# MI0283QT_v14.net
KiCad netlist of a schematic drawn in EAGLE
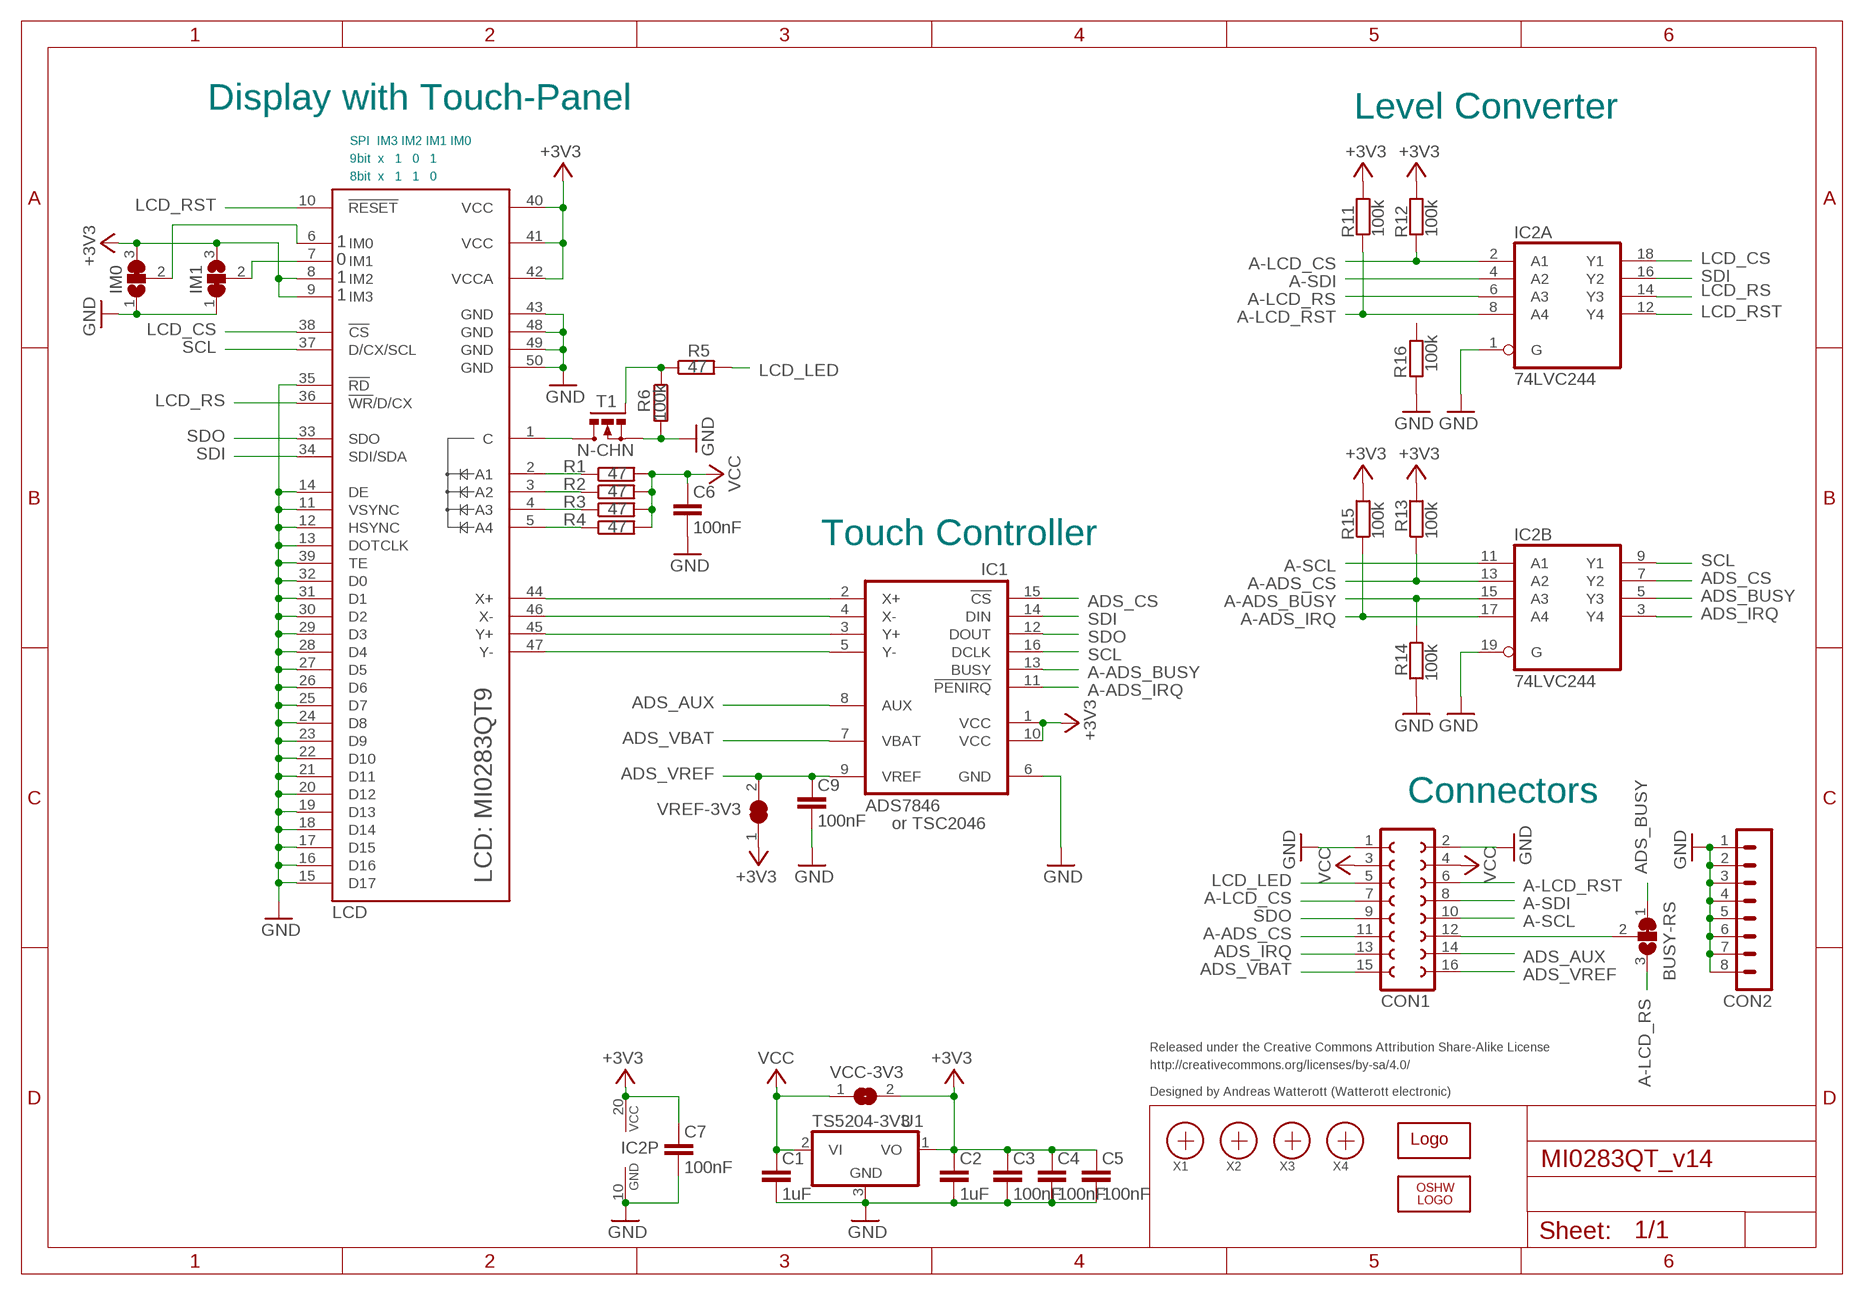
[diagram p0: schematic, sheet 1]

(export (version "E")
  (design (tool "Eeschema 10.0.6"))
  (components
    (comp (ref "BUSY-RS")
      (value "SJ2W")
      (footprint "eagle-import:SJ_2")
      (libsource (lib "eagle-import") (part "SJ2W"))
    )
    (comp (ref "C1")
      (value "1uF")
      (footprint "eagle-import:C0603")
      (libsource (lib "eagle-import") (part "C-EUC0603"))
    )
    (comp (ref "C2")
      (value "1uF")
      (footprint "eagle-import:C0603")
      (libsource (lib "eagle-import") (part "C-EUC0603"))
    )
    (comp (ref "C3")
      (value "100nF")
      (footprint "eagle-import:C0603")
      (libsource (lib "eagle-import") (part "C-EUC0603"))
    )
    (comp (ref "C4")
      (value "100nF")
      (footprint "eagle-import:C0603")
      (libsource (lib "eagle-import") (part "C-EUC0603"))
    )
    (comp (ref "C5")
      (value "100nF")
      (footprint "eagle-import:C0603")
      (libsource (lib "eagle-import") (part "C-EUC0603"))
    )
    (comp (ref "C6")
      (value "100nF")
      (footprint "eagle-import:C0603")
      (libsource (lib "eagle-import") (part "C-EUC0603"))
    )
    (comp (ref "C7")
      (value "100nF")
      (footprint "eagle-import:C0603")
      (libsource (lib "eagle-import") (part "C-EUC0603"))
    )
    (comp (ref "C9")
      (value "100nF")
      (footprint "eagle-import:C0603")
      (libsource (lib "eagle-import") (part "C-EUC0603"))
    )
    (comp (ref "CON1")
      (value "FE08-2")
      (footprint "eagle-import:FE08-2")
      (libsource (lib "eagle-import") (part "FE08-2"))
    )
    (comp (ref "CON2")
      (value "MA08-1")
      (footprint "eagle-import:MA08-1")
      (libsource (lib "eagle-import") (part "MA08-1"))
    )
    (comp (ref "IC1")
      (value "ADS7846")
      (footprint "eagle-import:SSOP16")
      (libsource (lib "eagle-import") (part "ADS7846"))
    )
    (comp (ref "IC2")
      (value "74LVC244")
      (footprint "eagle-import:SO20W")
      (libsource (lib "eagle-import") (part "74244DWHC"))
    )
    (comp (ref "IM0")
      (value "SJ2W")
      (footprint "eagle-import:SJ_2")
      (libsource (lib "eagle-import") (part "SJ2W"))
    )
    (comp (ref "IM1")
      (value "SJ2W")
      (footprint "eagle-import:SJ_2")
      (libsource (lib "eagle-import") (part "SJ2W"))
    )
    (comp (ref "LCD")
      (value "MI0283QT9")
      (footprint "eagle-import:MI0283QT9")
      (libsource (lib "eagle-import") (part "MI0283QT9"))
    )
    (comp (ref "LOGO1")
      (value "OSHW_LOGO_6MILX0150-NT")
      (footprint "eagle-import:OSHW_6X150_NOTEXT")
      (libsource (lib "eagle-import") (part "OSHW_LOGO_6MILX0150-NT"))
    )
    (comp (ref "R1")
      (value "47")
      (footprint "eagle-import:R0603")
      (libsource (lib "eagle-import") (part "R-EU_R0603"))
    )
    (comp (ref "R2")
      (value "47")
      (footprint "eagle-import:R0603")
      (libsource (lib "eagle-import") (part "R-EU_R0603"))
    )
    (comp (ref "R3")
      (value "47")
      (footprint "eagle-import:R0603")
      (libsource (lib "eagle-import") (part "R-EU_R0603"))
    )
    (comp (ref "R4")
      (value "47")
      (footprint "eagle-import:R0603")
      (libsource (lib "eagle-import") (part "R-EU_R0603"))
    )
    (comp (ref "R5")
      (value "47")
      (footprint "eagle-import:R0603")
      (libsource (lib "eagle-import") (part "R-EU_R0603"))
    )
    (comp (ref "R6")
      (value "100k")
      (footprint "eagle-import:R0603")
      (libsource (lib "eagle-import") (part "R-EU_R0603"))
    )
    (comp (ref "R11")
      (value "100k")
      (footprint "eagle-import:R0603")
      (libsource (lib "eagle-import") (part "R-EU_R0603"))
    )
    (comp (ref "R12")
      (value "100k")
      (footprint "eagle-import:R0603")
      (libsource (lib "eagle-import") (part "R-EU_R0603"))
    )
    (comp (ref "R13")
      (value "100k")
      (footprint "eagle-import:R0603")
      (libsource (lib "eagle-import") (part "R-EU_R0603"))
    )
    (comp (ref "R14")
      (value "100k")
      (footprint "eagle-import:R0603")
      (libsource (lib "eagle-import") (part "R-EU_R0603"))
    )
    (comp (ref "R15")
      (value "100k")
      (footprint "eagle-import:R0603")
      (libsource (lib "eagle-import") (part "R-EU_R0603"))
    )
    (comp (ref "R16")
      (value "100k")
      (footprint "eagle-import:R0603")
      (libsource (lib "eagle-import") (part "R-EU_R0603"))
    )
    (comp (ref "T1")
      (value "N-CHN")
      (footprint "eagle-import:MICRO3")
      (libsource (lib "eagle-import") (part "IRLML2502"))
    )
    (comp (ref "U$1")
      (value "WE-LOGO")
      (footprint "eagle-import:WE-LOGO")
      (libsource (lib "eagle-import") (part "WE-LOGOPLACE"))
    )
    (comp (ref "U1")
      (value "TS5204-3V3")
      (footprint "eagle-import:SOT23")
      (libsource (lib "eagle-import") (part "TS5204"))
    )
    (comp (ref "VCC-3V3")
      (value "SJ")
      (footprint "eagle-import:SJ")
      (libsource (lib "eagle-import") (part "SJ"))
    )
    (comp (ref "VREF-3V3")
      (value "SJ")
      (footprint "eagle-import:SJ")
      (libsource (lib "eagle-import") (part "SJ"))
    )
    (comp (ref "X1")
      (value "PASSER")
      (footprint "eagle-import:PASSER")
      (libsource (lib "eagle-import") (part "PASSER"))
    )
    (comp (ref "X2")
      (value "PASSER")
      (footprint "eagle-import:PASSER")
      (libsource (lib "eagle-import") (part "PASSER"))
    )
    (comp (ref "X3")
      (value "PASSER")
      (footprint "eagle-import:PASSER")
      (libsource (lib "eagle-import") (part "PASSER"))
    )
    (comp (ref "X4")
      (value "PASSER")
      (footprint "eagle-import:PASSER")
      (libsource (lib "eagle-import") (part "PASSER"))
    )
  )
  (nets
    (net (code "1") (name "+3V3") (class "Default")
      (node (ref "C2") (pin "1") (pinfunction "1_1") (pintype "passive"))
      (node (ref "C3") (pin "1") (pinfunction "1_1") (pintype "passive"))
      (node (ref "C4") (pin "1") (pinfunction "1_1") (pintype "passive"))
      (node (ref "C5") (pin "1") (pinfunction "1_1") (pintype "passive"))
      (node (ref "C7") (pin "1") (pinfunction "1_1") (pintype "passive"))
      (node (ref "IC1") (pin "1") (pinfunction "VCC_1") (pintype "power_in"))
      (node (ref "IC1") (pin "10") (pinfunction "VCC_10") (pintype "power_in"))
      (node (ref "IC2") (pin "20") (pinfunction "VCC_20") (pintype "power_in"))
      (node (ref "IM0") (pin "3") (pinfunction "3_3") (pintype "passive"))
      (node (ref "IM1") (pin "3") (pinfunction "3_3") (pintype "passive"))
      (node (ref "LCD") (pin "40") (pinfunction "VCC_40") (pintype "power_in"))
      (node (ref "LCD") (pin "41") (pinfunction "VCC_41") (pintype "power_in"))
      (node (ref "LCD") (pin "42") (pinfunction "VCCA_42") (pintype "power_in"))
      (node (ref "LCD") (pin "8") (pinfunction "IM2_8") (pintype "input"))
      (node (ref "LCD") (pin "9") (pinfunction "IM3_9") (pintype "input"))
      (node (ref "R11") (pin "2") (pinfunction "2_2") (pintype "passive"))
      (node (ref "R12") (pin "2") (pinfunction "2_2") (pintype "passive"))
      (node (ref "R13") (pin "2") (pinfunction "2_2") (pintype "passive"))
      (node (ref "R15") (pin "2") (pinfunction "2_2") (pintype "passive"))
      (node (ref "U1") (pin "1") (pinfunction "VO_1") (pintype "passive"))
      (node (ref "VCC-3V3") (pin "2") (pinfunction "2_2") (pintype "passive"))
      (node (ref "VREF-3V3") (pin "1") (pinfunction "1_1") (pintype "passive"))
    )
    (net (code "2") (name "/A-ADS_BUSY") (class "Default")
      (node (ref "IC1") (pin "13") (pinfunction "BUSY_13") (pintype "output"))
      (node (ref "IC2") (pin "15") (pinfunction "A3_15") (pintype "input"))
      (node (ref "R14") (pin "1") (pinfunction "1_1") (pintype "passive"))
    )
    (net (code "3") (name "/A-ADS_CS") (class "Default")
      (node (ref "CON1") (pin "11") (pinfunction "11_11") (pintype "passive"))
      (node (ref "IC2") (pin "13") (pinfunction "A2_13") (pintype "input"))
      (node (ref "R13") (pin "1") (pinfunction "1_1") (pintype "passive"))
    )
    (net (code "4") (name "/A-ADS_IRQ") (class "Default")
      (node (ref "IC1") (pin "11") (pinfunction "~{PENIRQ}_11") (pintype "output"))
      (node (ref "IC2") (pin "17") (pinfunction "A4_17") (pintype "input"))
      (node (ref "R15") (pin "1") (pinfunction "1_1") (pintype "passive"))
    )
    (net (code "5") (name "/A-LCD_CS") (class "Default")
      (node (ref "CON1") (pin "7") (pinfunction "7_7") (pintype "passive"))
      (node (ref "IC2") (pin "2") (pinfunction "A1_2") (pintype "input"))
      (node (ref "R12") (pin "1") (pinfunction "1_1") (pintype "passive"))
    )
    (net (code "6") (name "/A-LCD_RS") (class "Default")
      (node (ref "BUSY-RS") (pin "3") (pinfunction "3_3") (pintype "passive"))
      (node (ref "IC2") (pin "6") (pinfunction "A3_6") (pintype "input"))
    )
    (net (code "7") (name "/A-LCD_RST") (class "Default")
      (node (ref "CON1") (pin "6") (pinfunction "6_6") (pintype "passive"))
      (node (ref "IC2") (pin "8") (pinfunction "A4_8") (pintype "input"))
      (node (ref "R11") (pin "1") (pinfunction "1_1") (pintype "passive"))
    )
    (net (code "8") (name "/A-SCL") (class "Default")
      (node (ref "CON1") (pin "10") (pinfunction "10_10") (pintype "passive"))
      (node (ref "IC2") (pin "11") (pinfunction "A1_11") (pintype "input"))
    )
    (net (code "9") (name "/A-SDI") (class "Default")
      (node (ref "CON1") (pin "8") (pinfunction "8_8") (pintype "passive"))
      (node (ref "IC2") (pin "4") (pinfunction "A2_4") (pintype "input"))
    )
    (net (code "10") (name "/ADS_AUX") (class "Default")
      (node (ref "CON1") (pin "14") (pinfunction "14_14") (pintype "passive"))
      (node (ref "IC1") (pin "8") (pinfunction "AUX_8") (pintype "input"))
    )
    (net (code "11") (name "/ADS_BUSY") (class "Default")
      (node (ref "BUSY-RS") (pin "1") (pinfunction "1_1") (pintype "passive"))
      (node (ref "IC2") (pin "5") (pinfunction "Y3_5") (pintype "tri_state"))
    )
    (net (code "12") (name "/ADS_CS") (class "Default")
      (node (ref "IC1") (pin "15") (pinfunction "~{CS}_15") (pintype "input"))
      (node (ref "IC2") (pin "7") (pinfunction "Y2_7") (pintype "tri_state"))
    )
    (net (code "13") (name "/ADS_IRQ") (class "Default")
      (node (ref "CON1") (pin "13") (pinfunction "13_13") (pintype "passive"))
      (node (ref "IC2") (pin "3") (pinfunction "Y4_3") (pintype "tri_state"))
    )
    (net (code "14") (name "/ADS_VBAT") (class "Default")
      (node (ref "CON1") (pin "15") (pinfunction "15_15") (pintype "passive"))
      (node (ref "IC1") (pin "7") (pinfunction "VBAT_7") (pintype "input"))
    )
    (net (code "15") (name "/ADS_VREF") (class "Default")
      (node (ref "C9") (pin "1") (pinfunction "1_1") (pintype "passive"))
      (node (ref "CON1") (pin "16") (pinfunction "16_16") (pintype "passive"))
      (node (ref "IC1") (pin "9") (pinfunction "VREF_9") (pintype "bidirectional"))
      (node (ref "VREF-3V3") (pin "2") (pinfunction "2_2") (pintype "passive"))
    )
    (net (code "16") (name "/LCD_CS") (class "Default")
      (node (ref "IC2") (pin "18") (pinfunction "Y1_18") (pintype "tri_state"))
      (node (ref "LCD") (pin "38") (pinfunction "~{CS}_38") (pintype "input"))
    )
    (net (code "17") (name "/LCD_LED") (class "Default")
      (node (ref "CON1") (pin "5") (pinfunction "5_5") (pintype "passive"))
      (node (ref "R5") (pin "2") (pinfunction "2_2") (pintype "passive"))
    )
    (net (code "18") (name "/LCD_RS") (class "Default")
      (node (ref "IC2") (pin "14") (pinfunction "Y3_14") (pintype "tri_state"))
      (node (ref "LCD") (pin "36") (pinfunction "~{WR}/D/CX_36") (pintype "input"))
    )
    (net (code "19") (name "/LCD_RST") (class "Default")
      (node (ref "IC2") (pin "12") (pinfunction "Y4_12") (pintype "tri_state"))
      (node (ref "LCD") (pin "10") (pinfunction "~{RESET}_10") (pintype "input"))
    )
    (net (code "20") (name "/SCL") (class "Default")
      (node (ref "IC1") (pin "16") (pinfunction "DCLK_16") (pintype "output"))
      (node (ref "IC2") (pin "9") (pinfunction "Y1_9") (pintype "tri_state"))
      (node (ref "LCD") (pin "37") (pinfunction "D/CX/SCL_37") (pintype "input"))
    )
    (net (code "21") (name "/SDI") (class "Default")
      (node (ref "IC1") (pin "14") (pinfunction "DIN_14") (pintype "input"))
      (node (ref "IC2") (pin "16") (pinfunction "Y2_16") (pintype "tri_state"))
      (node (ref "LCD") (pin "34") (pinfunction "SDI/SDA_34") (pintype "input"))
    )
    (net (code "22") (name "/SDO") (class "Default")
      (node (ref "CON1") (pin "9") (pinfunction "9_9") (pintype "passive"))
      (node (ref "IC1") (pin "12") (pinfunction "DOUT_12") (pintype "input"))
      (node (ref "LCD") (pin "33") (pinfunction "SDO_33") (pintype "output"))
    )
    (net (code "23") (name "GND") (class "Default")
      (node (ref "C1") (pin "2") (pinfunction "2_2") (pintype "passive"))
      (node (ref "C2") (pin "2") (pinfunction "2_2") (pintype "passive"))
      (node (ref "C3") (pin "2") (pinfunction "2_2") (pintype "passive"))
      (node (ref "C4") (pin "2") (pinfunction "2_2") (pintype "passive"))
      (node (ref "C5") (pin "2") (pinfunction "2_2") (pintype "passive"))
      (node (ref "C6") (pin "2") (pinfunction "2_2") (pintype "passive"))
      (node (ref "C7") (pin "2") (pinfunction "2_2") (pintype "passive"))
      (node (ref "C9") (pin "2") (pinfunction "2_2") (pintype "passive"))
      (node (ref "CON1") (pin "1") (pinfunction "1_1") (pintype "passive"))
      (node (ref "CON1") (pin "2") (pinfunction "2_2") (pintype "passive"))
      (node (ref "CON2") (pin "1") (pinfunction "1_1") (pintype "passive"))
      (node (ref "CON2") (pin "2") (pinfunction "2_2") (pintype "passive"))
      (node (ref "CON2") (pin "3") (pinfunction "3_3") (pintype "passive"))
      (node (ref "CON2") (pin "4") (pinfunction "4_4") (pintype "passive"))
      (node (ref "CON2") (pin "5") (pinfunction "5_5") (pintype "passive"))
      (node (ref "CON2") (pin "6") (pinfunction "6_6") (pintype "passive"))
      (node (ref "CON2") (pin "7") (pinfunction "7_7") (pintype "passive"))
      (node (ref "CON2") (pin "8") (pinfunction "8_8") (pintype "passive"))
      (node (ref "IC1") (pin "6") (pinfunction "GND_6") (pintype "power_in"))
      (node (ref "IC2") (pin "1") (pinfunction "G_1") (pintype "input"))
      (node (ref "IC2") (pin "10") (pinfunction "GND_10") (pintype "power_in"))
      (node (ref "IC2") (pin "19") (pinfunction "G_19") (pintype "input"))
      (node (ref "IM0") (pin "1") (pinfunction "1_1") (pintype "passive"))
      (node (ref "IM1") (pin "1") (pinfunction "1_1") (pintype "passive"))
      (node (ref "LCD") (pin "11") (pinfunction "VSYNC_11") (pintype "input"))
      (node (ref "LCD") (pin "12") (pinfunction "HSYNC_12") (pintype "input"))
      (node (ref "LCD") (pin "13") (pinfunction "DOTCLK_13") (pintype "input"))
      (node (ref "LCD") (pin "14") (pinfunction "DE_14") (pintype "input"))
      (node (ref "LCD") (pin "15") (pinfunction "D17_15") (pintype "input"))
      (node (ref "LCD") (pin "16") (pinfunction "D16_16") (pintype "input"))
      (node (ref "LCD") (pin "17") (pinfunction "D15_17") (pintype "input"))
      (node (ref "LCD") (pin "18") (pinfunction "D14_18") (pintype "input"))
      (node (ref "LCD") (pin "19") (pinfunction "D13_19") (pintype "input"))
      (node (ref "LCD") (pin "20") (pinfunction "D12_20") (pintype "input"))
      (node (ref "LCD") (pin "21") (pinfunction "D11_21") (pintype "input"))
      (node (ref "LCD") (pin "22") (pinfunction "D10_22") (pintype "input"))
      (node (ref "LCD") (pin "23") (pinfunction "D9_23") (pintype "input"))
      (node (ref "LCD") (pin "24") (pinfunction "D8_24") (pintype "input"))
      (node (ref "LCD") (pin "25") (pinfunction "D7_25") (pintype "input"))
      (node (ref "LCD") (pin "26") (pinfunction "D6_26") (pintype "input"))
      (node (ref "LCD") (pin "27") (pinfunction "D5_27") (pintype "input"))
      (node (ref "LCD") (pin "28") (pinfunction "D4_28") (pintype "input"))
      (node (ref "LCD") (pin "29") (pinfunction "D3_29") (pintype "input"))
      (node (ref "LCD") (pin "30") (pinfunction "D2_30") (pintype "input"))
      (node (ref "LCD") (pin "31") (pinfunction "D1_31") (pintype "input"))
      (node (ref "LCD") (pin "32") (pinfunction "D0_32") (pintype "input"))
      (node (ref "LCD") (pin "35") (pinfunction "~{RD}_35") (pintype "input"))
      (node (ref "LCD") (pin "39") (pinfunction "TE_39") (pintype "output"))
      (node (ref "LCD") (pin "43") (pinfunction "GND_43") (pintype "power_in"))
      (node (ref "LCD") (pin "48") (pinfunction "GND_48") (pintype "power_in"))
      (node (ref "LCD") (pin "49") (pinfunction "GND_49") (pintype "power_in"))
      (node (ref "LCD") (pin "50") (pinfunction "GND_50") (pintype "power_in"))
      (node (ref "R14") (pin "2") (pinfunction "2_2") (pintype "passive"))
      (node (ref "R16") (pin "2") (pinfunction "2_2") (pintype "passive"))
      (node (ref "R6") (pin "2") (pinfunction "2_2") (pintype "passive"))
      (node (ref "T1") (pin "2") (pinfunction "S_2") (pintype "passive"))
      (node (ref "U1") (pin "3") (pinfunction "GND_3") (pintype "passive"))
    )
    (net (code "24") (name "Net-(BUSY-RS-Pad2)") (class "Default")
      (node (ref "BUSY-RS") (pin "2") (pinfunction "2_2") (pintype "passive"))
      (node (ref "CON1") (pin "12") (pinfunction "12_12") (pintype "passive"))
    )
    (net (code "25") (name "Net-(IC1-X+)") (class "Default")
      (node (ref "IC1") (pin "2") (pinfunction "X+_2") (pintype "input"))
      (node (ref "LCD") (pin "44") (pinfunction "X+_44") (pintype "passive"))
    )
    (net (code "26") (name "Net-(IC1-X-)") (class "Default")
      (node (ref "IC1") (pin "4") (pinfunction "X-_4") (pintype "input"))
      (node (ref "LCD") (pin "46") (pinfunction "X-_46") (pintype "passive"))
    )
    (net (code "27") (name "Net-(IC1-Y+)") (class "Default")
      (node (ref "IC1") (pin "3") (pinfunction "Y+_3") (pintype "input"))
      (node (ref "LCD") (pin "45") (pinfunction "Y+_45") (pintype "passive"))
    )
    (net (code "28") (name "Net-(IC1-Y-)") (class "Default")
      (node (ref "IC1") (pin "5") (pinfunction "Y-_5") (pintype "input"))
      (node (ref "LCD") (pin "47") (pinfunction "Y-_47") (pintype "passive"))
    )
    (net (code "29") (name "Net-(LCD-A1)") (class "Default")
      (node (ref "LCD") (pin "2") (pinfunction "A1_2") (pintype "power_in"))
      (node (ref "R1") (pin "1") (pinfunction "1_1") (pintype "passive"))
    )
    (net (code "30") (name "Net-(LCD-A2)") (class "Default")
      (node (ref "LCD") (pin "3") (pinfunction "A2_3") (pintype "power_in"))
      (node (ref "R2") (pin "1") (pinfunction "1_1") (pintype "passive"))
    )
    (net (code "31") (name "Net-(LCD-A3)") (class "Default")
      (node (ref "LCD") (pin "4") (pinfunction "A3_4") (pintype "power_in"))
      (node (ref "R3") (pin "1") (pinfunction "1_1") (pintype "passive"))
    )
    (net (code "32") (name "Net-(LCD-A4)") (class "Default")
      (node (ref "LCD") (pin "5") (pinfunction "A4_5") (pintype "power_in"))
      (node (ref "R4") (pin "1") (pinfunction "1_1") (pintype "passive"))
    )
    (net (code "33") (name "Net-(LCD-C)") (class "Default")
      (node (ref "LCD") (pin "1") (pinfunction "C_1") (pintype "power_in"))
      (node (ref "T1") (pin "3") (pinfunction "D_3") (pintype "passive"))
    )
    (net (code "34") (name "Net-(LCD-IM0)") (class "Default")
      (node (ref "IM0") (pin "2") (pinfunction "2_2") (pintype "passive"))
      (node (ref "LCD") (pin "6") (pinfunction "IM0_6") (pintype "input"))
    )
    (net (code "35") (name "Net-(LCD-IM1)") (class "Default")
      (node (ref "IM1") (pin "2") (pinfunction "2_2") (pintype "passive"))
      (node (ref "LCD") (pin "7") (pinfunction "IM1_7") (pintype "input"))
    )
    (net (code "36") (name "Net-(T1-G)") (class "Default")
      (node (ref "R5") (pin "1") (pinfunction "1_1") (pintype "passive"))
      (node (ref "R6") (pin "1") (pinfunction "1_1") (pintype "passive"))
      (node (ref "T1") (pin "1") (pinfunction "G_1") (pintype "passive"))
    )
    (net (code "37") (name "VCC") (class "Default")
      (node (ref "C1") (pin "1") (pinfunction "1_1") (pintype "passive"))
      (node (ref "C6") (pin "1") (pinfunction "1_1") (pintype "passive"))
      (node (ref "CON1") (pin "3") (pinfunction "3_3") (pintype "passive"))
      (node (ref "CON1") (pin "4") (pinfunction "4_4") (pintype "passive"))
      (node (ref "R1") (pin "2") (pinfunction "2_2") (pintype "passive"))
      (node (ref "R2") (pin "2") (pinfunction "2_2") (pintype "passive"))
      (node (ref "R3") (pin "2") (pinfunction "2_2") (pintype "passive"))
      (node (ref "R4") (pin "2") (pinfunction "2_2") (pintype "passive"))
      (node (ref "U1") (pin "2") (pinfunction "VI_2") (pintype "input"))
      (node (ref "VCC-3V3") (pin "1") (pinfunction "1_1") (pintype "passive"))
    )
    (net (code "38") (name "unconnected-(R16-Pad1)") (class "Default")
      (node (ref "R16") (pin "1") (pinfunction "1_1") (pintype "passive"))
    )
  )
)
